# solenoid.net
KiCad netlist of a schematic drawn in Altium Designer
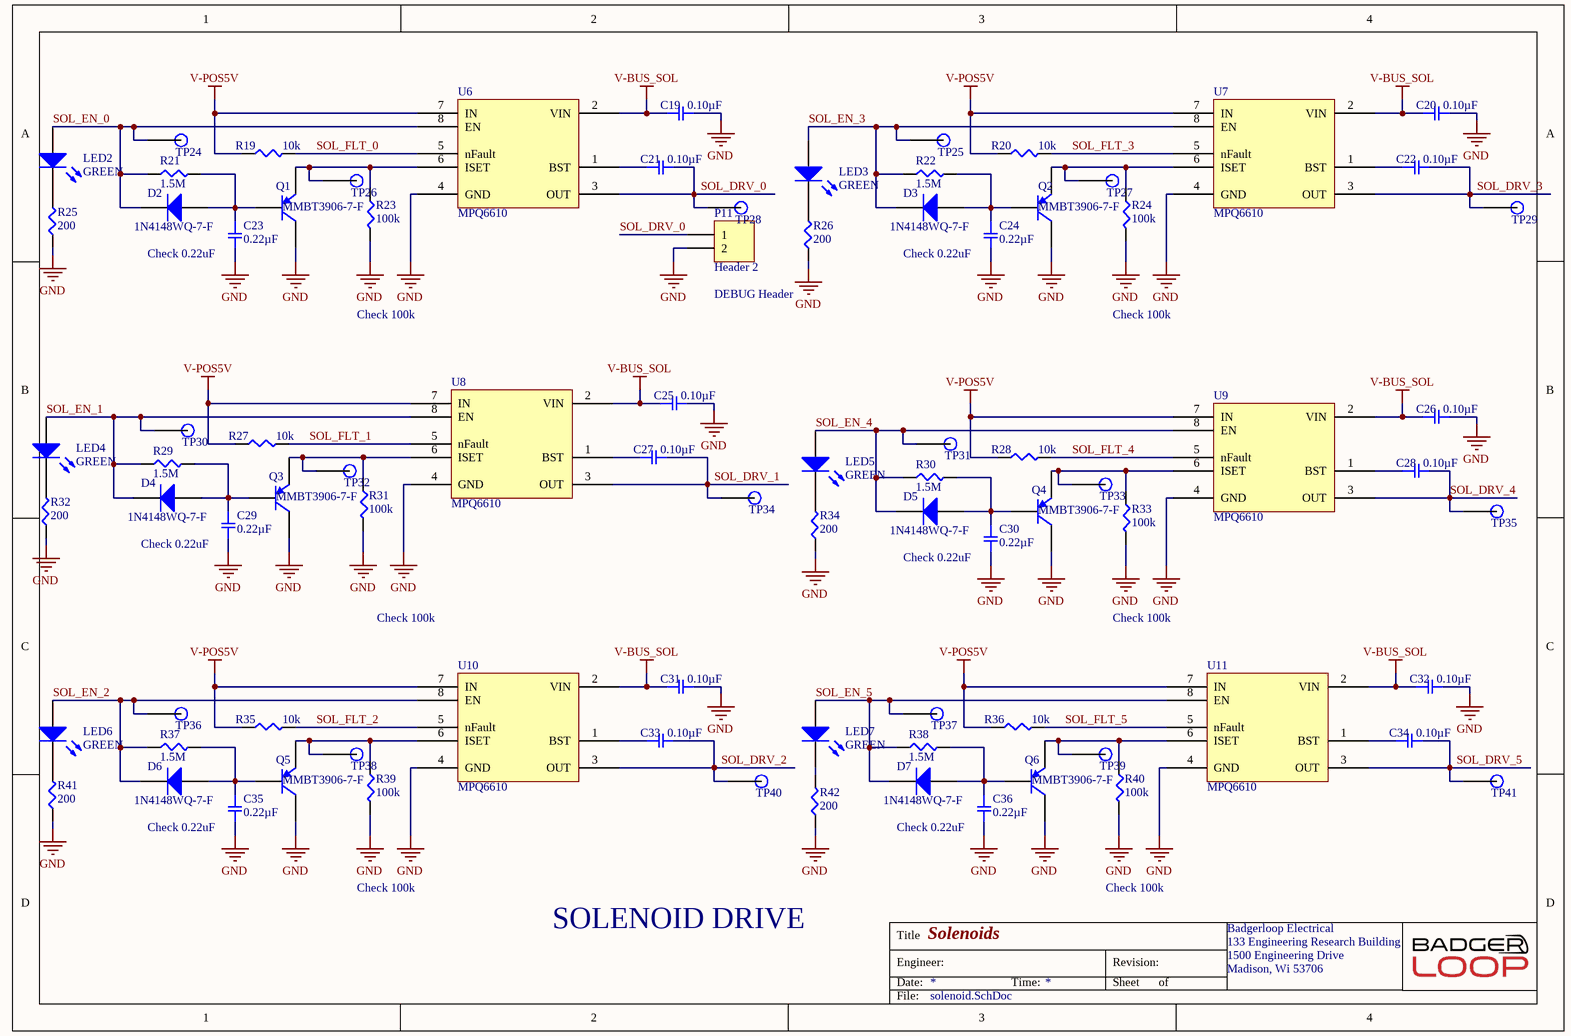
[diagram p0: solenoid.SchDoc]

(export (version "E")
  (design (tool "Eeschema 10.0.6"))
  (components
    (comp (ref "C19")
      (value "0.10µF")
      (footprint "SMD-0805C")
      (description "CAP CER 0.1UF 10V U2J 0805")
      (fields
        (field (name "DIGI-KEY PART NUMBER") "490-11592-1-ND")
        (field (name "PART NUMBER") "GRM21B7U1A104JA01L")
      )
      (libsource (lib "capacitors") (part "GRM21B7U1A104JA01L"))
    )
    (comp (ref "C20")
      (value "0.10µF")
      (footprint "SMD-0805C")
      (description "CAP CER 0.1UF 10V U2J 0805")
      (fields
        (field (name "DIGI-KEY PART NUMBER") "490-11592-1-ND")
        (field (name "PART NUMBER") "GRM21B7U1A104JA01L")
      )
      (libsource (lib "capacitors") (part "GRM21B7U1A104JA01L"))
    )
    (comp (ref "C21")
      (value "0.10µF")
      (footprint "SMD-0805C")
      (description "CAP CER 0.1UF 10V U2J 0805")
      (fields
        (field (name "DIGI-KEY PART NUMBER") "490-11592-1-ND")
        (field (name "PART NUMBER") "GRM21B7U1A104JA01L")
      )
      (libsource (lib "capacitors") (part "GRM21B7U1A104JA01L"))
    )
    (comp (ref "C22")
      (value "0.10µF")
      (footprint "SMD-0805C")
      (description "CAP CER 0.1UF 10V U2J 0805")
      (fields
        (field (name "DIGI-KEY PART NUMBER") "490-11592-1-ND")
        (field (name "PART NUMBER") "GRM21B7U1A104JA01L")
      )
      (libsource (lib "capacitors") (part "GRM21B7U1A104JA01L"))
    )
    (comp (ref "C23")
      (value "0.22µF")
      (footprint "SMD-0805C")
      (description "CAP CER 0.22UF 10V X7R 0805")
      (fields
        (field (name "DIGI-KEY PART NUMBER") "490-4432-1-ND")
        (field (name "PART NUMBER") "LLA215R71A224MA14L")
      )
      (libsource (lib "capacitors") (part "LLA215R71A224MA14L"))
    )
    (comp (ref "C24")
      (value "0.22µF")
      (footprint "SMD-0805C")
      (description "CAP CER 0.22UF 10V X7R 0805")
      (fields
        (field (name "DIGI-KEY PART NUMBER") "490-4432-1-ND")
        (field (name "PART NUMBER") "LLA215R71A224MA14L")
      )
      (libsource (lib "capacitors") (part "LLA215R71A224MA14L"))
    )
    (comp (ref "C25")
      (value "0.10µF")
      (footprint "SMD-0805C")
      (description "CAP CER 0.1UF 10V U2J 0805")
      (fields
        (field (name "DIGI-KEY PART NUMBER") "490-11592-1-ND")
        (field (name "PART NUMBER") "GRM21B7U1A104JA01L")
      )
      (libsource (lib "capacitors") (part "GRM21B7U1A104JA01L"))
    )
    (comp (ref "C26")
      (value "0.10µF")
      (footprint "SMD-0805C")
      (description "CAP CER 0.1UF 10V U2J 0805")
      (fields
        (field (name "DIGI-KEY PART NUMBER") "490-11592-1-ND")
        (field (name "PART NUMBER") "GRM21B7U1A104JA01L")
      )
      (libsource (lib "capacitors") (part "GRM21B7U1A104JA01L"))
    )
    (comp (ref "C27")
      (value "0.10µF")
      (footprint "SMD-0805C")
      (description "CAP CER 0.1UF 10V U2J 0805")
      (fields
        (field (name "DIGI-KEY PART NUMBER") "490-11592-1-ND")
        (field (name "PART NUMBER") "GRM21B7U1A104JA01L")
      )
      (libsource (lib "capacitors") (part "GRM21B7U1A104JA01L"))
    )
    (comp (ref "C28")
      (value "0.10µF")
      (footprint "SMD-0805C")
      (description "CAP CER 0.1UF 10V U2J 0805")
      (fields
        (field (name "DIGI-KEY PART NUMBER") "490-11592-1-ND")
        (field (name "PART NUMBER") "GRM21B7U1A104JA01L")
      )
      (libsource (lib "capacitors") (part "GRM21B7U1A104JA01L"))
    )
    (comp (ref "C29")
      (value "0.22µF")
      (footprint "SMD-0805C")
      (description "CAP CER 0.22UF 10V X7R 0805")
      (fields
        (field (name "DIGI-KEY PART NUMBER") "490-4432-1-ND")
        (field (name "PART NUMBER") "LLA215R71A224MA14L")
      )
      (libsource (lib "capacitors") (part "LLA215R71A224MA14L"))
    )
    (comp (ref "C30")
      (value "0.22µF")
      (footprint "SMD-0805C")
      (description "CAP CER 0.22UF 10V X7R 0805")
      (fields
        (field (name "DIGI-KEY PART NUMBER") "490-4432-1-ND")
        (field (name "PART NUMBER") "LLA215R71A224MA14L")
      )
      (libsource (lib "capacitors") (part "LLA215R71A224MA14L"))
    )
    (comp (ref "C31")
      (value "0.10µF")
      (footprint "SMD-0805C")
      (description "CAP CER 0.1UF 10V U2J 0805")
      (fields
        (field (name "DIGI-KEY PART NUMBER") "490-11592-1-ND")
        (field (name "PART NUMBER") "GRM21B7U1A104JA01L")
      )
      (libsource (lib "capacitors") (part "GRM21B7U1A104JA01L"))
    )
    (comp (ref "C32")
      (value "0.10µF")
      (footprint "SMD-0805C")
      (description "CAP CER 0.1UF 10V U2J 0805")
      (fields
        (field (name "DIGI-KEY PART NUMBER") "490-11592-1-ND")
        (field (name "PART NUMBER") "GRM21B7U1A104JA01L")
      )
      (libsource (lib "capacitors") (part "GRM21B7U1A104JA01L"))
    )
    (comp (ref "C33")
      (value "0.10µF")
      (footprint "SMD-0805C")
      (description "CAP CER 0.1UF 10V U2J 0805")
      (fields
        (field (name "DIGI-KEY PART NUMBER") "490-11592-1-ND")
        (field (name "PART NUMBER") "GRM21B7U1A104JA01L")
      )
      (libsource (lib "capacitors") (part "GRM21B7U1A104JA01L"))
    )
    (comp (ref "C34")
      (value "0.10µF")
      (footprint "SMD-0805C")
      (description "CAP CER 0.1UF 10V U2J 0805")
      (fields
        (field (name "DIGI-KEY PART NUMBER") "490-11592-1-ND")
        (field (name "PART NUMBER") "GRM21B7U1A104JA01L")
      )
      (libsource (lib "capacitors") (part "GRM21B7U1A104JA01L"))
    )
    (comp (ref "C35")
      (value "0.22µF")
      (footprint "SMD-0805C")
      (description "CAP CER 0.22UF 10V X7R 0805")
      (fields
        (field (name "DIGI-KEY PART NUMBER") "490-4432-1-ND")
        (field (name "PART NUMBER") "LLA215R71A224MA14L")
      )
      (libsource (lib "capacitors") (part "LLA215R71A224MA14L"))
    )
    (comp (ref "C36")
      (value "0.22µF")
      (footprint "SMD-0805C")
      (description "CAP CER 0.22UF 10V X7R 0805")
      (fields
        (field (name "DIGI-KEY PART NUMBER") "490-4432-1-ND")
        (field (name "PART NUMBER") "LLA215R71A224MA14L")
      )
      (libsource (lib "capacitors") (part "LLA215R71A224MA14L"))
    )
    (comp (ref "D2")
      (value "1N4148WQ-7-F")
      (footprint "SODFL350X80-2N")
      (description "Diodes - General Purpose, Power, Switching SMT Fast Switching Diode")
      (fields (field (name "MANUFACTURER") "Diodes Inc."))
      (libsource (lib "misc") (part "1N4148WQ-7-F"))
    )
    (comp (ref "D3")
      (value "1N4148WQ-7-F")
      (footprint "SODFL350X80-2N")
      (description "Diodes - General Purpose, Power, Switching SMT Fast Switching Diode")
      (fields (field (name "MANUFACTURER") "Diodes Inc."))
      (libsource (lib "misc") (part "1N4148WQ-7-F"))
    )
    (comp (ref "D4")
      (value "1N4148WQ-7-F")
      (footprint "SODFL350X80-2N")
      (description "Diodes - General Purpose, Power, Switching SMT Fast Switching Diode")
      (fields (field (name "MANUFACTURER") "Diodes Inc."))
      (libsource (lib "misc") (part "1N4148WQ-7-F"))
    )
    (comp (ref "D5")
      (value "1N4148WQ-7-F")
      (footprint "SODFL350X80-2N")
      (description "Diodes - General Purpose, Power, Switching SMT Fast Switching Diode")
      (fields (field (name "MANUFACTURER") "Diodes Inc."))
      (libsource (lib "misc") (part "1N4148WQ-7-F"))
    )
    (comp (ref "D6")
      (value "1N4148WQ-7-F")
      (footprint "SODFL350X80-2N")
      (description "Diodes - General Purpose, Power, Switching SMT Fast Switching Diode")
      (fields (field (name "MANUFACTURER") "Diodes Inc."))
      (libsource (lib "misc") (part "1N4148WQ-7-F"))
    )
    (comp (ref "D7")
      (value "1N4148WQ-7-F")
      (footprint "SODFL350X80-2N")
      (description "Diodes - General Purpose, Power, Switching SMT Fast Switching Diode")
      (fields (field (name "MANUFACTURER") "Diodes Inc."))
      (libsource (lib "misc") (part "1N4148WQ-7-F"))
    )
    (comp (ref "LED2")
      (value "GREEN")
      (footprint "LED 0603 GREEN")
      (fields (field (name "MANUFACTURER") "Lite-On Inc."))
      (libsource (lib "misc") (part "LED GREEN 0603"))
    )
    (comp (ref "LED3")
      (value "GREEN")
      (footprint "LED 0603 GREEN")
      (fields (field (name "MANUFACTURER") "Lite-On Inc."))
      (libsource (lib "misc") (part "LED GREEN 0603"))
    )
    (comp (ref "LED4")
      (value "GREEN")
      (footprint "LED 0603 GREEN")
      (fields (field (name "MANUFACTURER") "Lite-On Inc."))
      (libsource (lib "misc") (part "LED GREEN 0603"))
    )
    (comp (ref "LED5")
      (value "GREEN")
      (footprint "LED 0603 GREEN")
      (fields (field (name "MANUFACTURER") "Lite-On Inc."))
      (libsource (lib "misc") (part "LED GREEN 0603"))
    )
    (comp (ref "LED6")
      (value "GREEN")
      (footprint "LED 0603 GREEN")
      (fields (field (name "MANUFACTURER") "Lite-On Inc."))
      (libsource (lib "misc") (part "LED GREEN 0603"))
    )
    (comp (ref "LED7")
      (value "GREEN")
      (footprint "LED 0603 GREEN")
      (fields (field (name "MANUFACTURER") "Lite-On Inc."))
      (libsource (lib "misc") (part "LED GREEN 0603"))
    )
    (comp (ref "P11")
      (value "Header 2")
      (footprint "Pin Header 1x2 TH Pitch 2.54mm")
      (description "Header, 2-Pin")
      (fields (field (name "PUBLISHER") "Altium Limited"))
      (libsource (lib "connector") (part "Header 2"))
    )
    (comp (ref "Q1")
      (value "MMBT3906-7-F")
      (footprint "SOTFL103P240X110-3N")
      (fields (field (name "MANUFACTURER") "Diodes Zetex"))
      (libsource (lib "misc") (part "MMBT3906-7-F"))
    )
    (comp (ref "Q2")
      (value "MMBT3906-7-F")
      (footprint "SOTFL103P240X110-3N")
      (fields (field (name "MANUFACTURER") "Diodes Zetex"))
      (libsource (lib "misc") (part "MMBT3906-7-F"))
    )
    (comp (ref "Q3")
      (value "MMBT3906-7-F")
      (footprint "SOTFL103P240X110-3N")
      (fields (field (name "MANUFACTURER") "Diodes Zetex"))
      (libsource (lib "misc") (part "MMBT3906-7-F"))
    )
    (comp (ref "Q4")
      (value "MMBT3906-7-F")
      (footprint "SOTFL103P240X110-3N")
      (fields (field (name "MANUFACTURER") "Diodes Zetex"))
      (libsource (lib "misc") (part "MMBT3906-7-F"))
    )
    (comp (ref "Q5")
      (value "MMBT3906-7-F")
      (footprint "SOTFL103P240X110-3N")
      (fields (field (name "MANUFACTURER") "Diodes Zetex"))
      (libsource (lib "misc") (part "MMBT3906-7-F"))
    )
    (comp (ref "Q6")
      (value "MMBT3906-7-F")
      (footprint "SOTFL103P240X110-3N")
      (fields (field (name "MANUFACTURER") "Diodes Zetex"))
      (libsource (lib "misc") (part "MMBT3906-7-F"))
    )
    (comp (ref "R19")
      (value "10k")
      (footprint "SMD-0805-RES")
      (description "RES SMD 10K OHM 5% 1/2W 0805")
      (fields (field (name "PART NUMBER") "ERJ-P06J103V") (field (name "DIGI-KEY PART NUMBER") "P10KADCT-ND"))
      (libsource (lib "resistors") (part "ERJ-P06J103V"))
    )
    (comp (ref "R20")
      (value "10k")
      (footprint "SMD-0805-RES")
      (description "RES SMD 10K OHM 5% 1/2W 0805")
      (fields (field (name "PART NUMBER") "ERJ-P06J103V") (field (name "DIGI-KEY PART NUMBER") "P10KADCT-ND"))
      (libsource (lib "resistors") (part "ERJ-P06J103V"))
    )
    (comp (ref "R21")
      (value "1.5M")
      (footprint "SMD-0805-RES")
      (description "RES SMD 1.5M OHM 5% 1/8W 0805")
      (fields
        (field (name "PART NUMBER") "ERJ-6GEYJ155V")
        (field (name "DIGI-KEY PART NUMBER") "P1.5MACT-ND")
      )
      (libsource (lib "resistors") (part "ERJ-6GEYJ155V"))
    )
    (comp (ref "R22")
      (value "1.5M")
      (footprint "SMD-0805-RES")
      (description "RES SMD 1.5M OHM 5% 1/8W 0805")
      (fields
        (field (name "PART NUMBER") "ERJ-6GEYJ155V")
        (field (name "DIGI-KEY PART NUMBER") "P1.5MACT-ND")
      )
      (libsource (lib "resistors") (part "ERJ-6GEYJ155V"))
    )
    (comp (ref "R23")
      (value "100k")
      (footprint "SMD-0805-RES")
      (description "RES SMD 100K OHM 5% 1/2W 0805")
      (fields
        (field (name "PART NUMBER") "ERJ-P06J104V")
        (field (name "DIGI-KEY PART NUMBER") "P100KADCT-ND")
      )
      (libsource (lib "resistors") (part "ERJ-P06J104V"))
    )
    (comp (ref "R24")
      (value "100k")
      (footprint "SMD-0805-RES")
      (description "RES SMD 100K OHM 5% 1/2W 0805")
      (fields
        (field (name "PART NUMBER") "ERJ-P06J104V")
        (field (name "DIGI-KEY PART NUMBER") "P100KADCT-ND")
      )
      (libsource (lib "resistors") (part "ERJ-P06J104V"))
    )
    (comp (ref "R25")
      (value "200")
      (footprint "SMD-0805-RES")
      (description "RES SMD 200 OHM 1% 1/2W 0805")
      (fields
        (field (name "PART NUMBER") "ERJ-P06F2000V")
        (field (name "DIGI-KEY PART NUMBER") "P16064CT-ND")
      )
      (libsource (lib "resistors") (part "ERJ-P06F2000V"))
    )
    (comp (ref "R26")
      (value "200")
      (footprint "SMD-0805-RES")
      (description "RES SMD 200 OHM 1% 1/2W 0805")
      (fields
        (field (name "PART NUMBER") "ERJ-P06F2000V")
        (field (name "DIGI-KEY PART NUMBER") "P16064CT-ND")
      )
      (libsource (lib "resistors") (part "ERJ-P06F2000V"))
    )
    (comp (ref "R27")
      (value "10k")
      (footprint "SMD-0805-RES")
      (description "RES SMD 10K OHM 5% 1/2W 0805")
      (fields (field (name "PART NUMBER") "ERJ-P06J103V") (field (name "DIGI-KEY PART NUMBER") "P10KADCT-ND"))
      (libsource (lib "resistors") (part "ERJ-P06J103V"))
    )
    (comp (ref "R28")
      (value "10k")
      (footprint "SMD-0805-RES")
      (description "RES SMD 10K OHM 5% 1/2W 0805")
      (fields (field (name "PART NUMBER") "ERJ-P06J103V") (field (name "DIGI-KEY PART NUMBER") "P10KADCT-ND"))
      (libsource (lib "resistors") (part "ERJ-P06J103V"))
    )
    (comp (ref "R29")
      (value "1.5M")
      (footprint "SMD-0805-RES")
      (description "RES SMD 1.5M OHM 5% 1/8W 0805")
      (fields
        (field (name "PART NUMBER") "ERJ-6GEYJ155V")
        (field (name "DIGI-KEY PART NUMBER") "P1.5MACT-ND")
      )
      (libsource (lib "resistors") (part "ERJ-6GEYJ155V"))
    )
    (comp (ref "R30")
      (value "1.5M")
      (footprint "SMD-0805-RES")
      (description "RES SMD 1.5M OHM 5% 1/8W 0805")
      (fields
        (field (name "PART NUMBER") "ERJ-6GEYJ155V")
        (field (name "DIGI-KEY PART NUMBER") "P1.5MACT-ND")
      )
      (libsource (lib "resistors") (part "ERJ-6GEYJ155V"))
    )
    (comp (ref "R31")
      (value "100k")
      (footprint "SMD-0805-RES")
      (description "RES SMD 100K OHM 5% 1/2W 0805")
      (fields
        (field (name "PART NUMBER") "ERJ-P06J104V")
        (field (name "DIGI-KEY PART NUMBER") "P100KADCT-ND")
      )
      (libsource (lib "resistors") (part "ERJ-P06J104V"))
    )
    (comp (ref "R32")
      (value "200")
      (footprint "SMD-0805-RES")
      (description "RES SMD 200 OHM 1% 1/2W 0805")
      (fields
        (field (name "PART NUMBER") "ERJ-P06F2000V")
        (field (name "DIGI-KEY PART NUMBER") "P16064CT-ND")
      )
      (libsource (lib "resistors") (part "ERJ-P06F2000V"))
    )
    (comp (ref "R33")
      (value "100k")
      (footprint "SMD-0805-RES")
      (description "RES SMD 100K OHM 5% 1/2W 0805")
      (fields
        (field (name "PART NUMBER") "ERJ-P06J104V")
        (field (name "DIGI-KEY PART NUMBER") "P100KADCT-ND")
      )
      (libsource (lib "resistors") (part "ERJ-P06J104V"))
    )
    (comp (ref "R34")
      (value "200")
      (footprint "SMD-0805-RES")
      (description "RES SMD 200 OHM 1% 1/2W 0805")
      (fields
        (field (name "PART NUMBER") "ERJ-P06F2000V")
        (field (name "DIGI-KEY PART NUMBER") "P16064CT-ND")
      )
      (libsource (lib "resistors") (part "ERJ-P06F2000V"))
    )
    (comp (ref "R35")
      (value "10k")
      (footprint "SMD-0805-RES")
      (description "RES SMD 10K OHM 5% 1/2W 0805")
      (fields (field (name "PART NUMBER") "ERJ-P06J103V") (field (name "DIGI-KEY PART NUMBER") "P10KADCT-ND"))
      (libsource (lib "resistors") (part "ERJ-P06J103V"))
    )
    (comp (ref "R36")
      (value "10k")
      (footprint "SMD-0805-RES")
      (description "RES SMD 10K OHM 5% 1/2W 0805")
      (fields (field (name "PART NUMBER") "ERJ-P06J103V") (field (name "DIGI-KEY PART NUMBER") "P10KADCT-ND"))
      (libsource (lib "resistors") (part "ERJ-P06J103V"))
    )
    (comp (ref "R37")
      (value "1.5M")
      (footprint "SMD-0805-RES")
      (description "RES SMD 1.5M OHM 5% 1/8W 0805")
      (fields
        (field (name "PART NUMBER") "ERJ-6GEYJ155V")
        (field (name "DIGI-KEY PART NUMBER") "P1.5MACT-ND")
      )
      (libsource (lib "resistors") (part "ERJ-6GEYJ155V"))
    )
    (comp (ref "R38")
      (value "1.5M")
      (footprint "SMD-0805-RES")
      (description "RES SMD 1.5M OHM 5% 1/8W 0805")
      (fields
        (field (name "PART NUMBER") "ERJ-6GEYJ155V")
        (field (name "DIGI-KEY PART NUMBER") "P1.5MACT-ND")
      )
      (libsource (lib "resistors") (part "ERJ-6GEYJ155V"))
    )
    (comp (ref "R39")
      (value "100k")
      (footprint "SMD-0805-RES")
      (description "RES SMD 100K OHM 5% 1/2W 0805")
      (fields
        (field (name "PART NUMBER") "ERJ-P06J104V")
        (field (name "DIGI-KEY PART NUMBER") "P100KADCT-ND")
      )
      (libsource (lib "resistors") (part "ERJ-P06J104V"))
    )
    (comp (ref "R40")
      (value "100k")
      (footprint "SMD-0805-RES")
      (description "RES SMD 100K OHM 5% 1/2W 0805")
      (fields
        (field (name "PART NUMBER") "ERJ-P06J104V")
        (field (name "DIGI-KEY PART NUMBER") "P100KADCT-ND")
      )
      (libsource (lib "resistors") (part "ERJ-P06J104V"))
    )
    (comp (ref "R41")
      (value "200")
      (footprint "SMD-0805-RES")
      (description "RES SMD 200 OHM 1% 1/2W 0805")
      (fields
        (field (name "PART NUMBER") "ERJ-P06F2000V")
        (field (name "DIGI-KEY PART NUMBER") "P16064CT-ND")
      )
      (libsource (lib "resistors") (part "ERJ-P06F2000V"))
    )
    (comp (ref "R42")
      (value "200")
      (footprint "SMD-0805-RES")
      (description "RES SMD 200 OHM 1% 1/2W 0805")
      (fields
        (field (name "PART NUMBER") "ERJ-P06F2000V")
        (field (name "DIGI-KEY PART NUMBER") "P16064CT-ND")
      )
      (libsource (lib "resistors") (part "ERJ-P06F2000V"))
    )
    (comp (ref "TP24")
      (value "TP")
      (footprint "Test Point")
      (description "SMD TEST POINT")
      (libsource (lib "misc") (part "TP"))
    )
    (comp (ref "TP25")
      (value "TP")
      (footprint "Test Point")
      (description "SMD TEST POINT")
      (libsource (lib "misc") (part "TP"))
    )
    (comp (ref "TP26")
      (value "TP")
      (footprint "Test Point")
      (description "SMD TEST POINT")
      (libsource (lib "misc") (part "TP"))
    )
    (comp (ref "TP27")
      (value "TP")
      (footprint "Test Point")
      (description "SMD TEST POINT")
      (libsource (lib "misc") (part "TP"))
    )
    (comp (ref "TP28")
      (value "TP")
      (footprint "Test Point")
      (description "SMD TEST POINT")
      (libsource (lib "misc") (part "TP"))
    )
    (comp (ref "TP29")
      (value "TP")
      (footprint "Test Point")
      (description "SMD TEST POINT")
      (libsource (lib "misc") (part "TP"))
    )
    (comp (ref "TP30")
      (value "TP")
      (footprint "Test Point")
      (description "SMD TEST POINT")
      (libsource (lib "misc") (part "TP"))
    )
    (comp (ref "TP31")
      (value "TP")
      (footprint "Test Point")
      (description "SMD TEST POINT")
      (libsource (lib "misc") (part "TP"))
    )
    (comp (ref "TP32")
      (value "TP")
      (footprint "Test Point")
      (description "SMD TEST POINT")
      (libsource (lib "misc") (part "TP"))
    )
    (comp (ref "TP33")
      (value "TP")
      (footprint "Test Point")
      (description "SMD TEST POINT")
      (libsource (lib "misc") (part "TP"))
    )
    (comp (ref "TP34")
      (value "TP")
      (footprint "Test Point")
      (description "SMD TEST POINT")
      (libsource (lib "misc") (part "TP"))
    )
    (comp (ref "TP35")
      (value "TP")
      (footprint "Test Point")
      (description "SMD TEST POINT")
      (libsource (lib "misc") (part "TP"))
    )
    (comp (ref "TP36")
      (value "TP")
      (footprint "Test Point")
      (description "SMD TEST POINT")
      (libsource (lib "misc") (part "TP"))
    )
    (comp (ref "TP37")
      (value "TP")
      (footprint "Test Point")
      (description "SMD TEST POINT")
      (libsource (lib "misc") (part "TP"))
    )
    (comp (ref "TP38")
      (value "TP")
      (footprint "Test Point")
      (description "SMD TEST POINT")
      (libsource (lib "misc") (part "TP"))
    )
    (comp (ref "TP39")
      (value "TP")
      (footprint "Test Point")
      (description "SMD TEST POINT")
      (libsource (lib "misc") (part "TP"))
    )
    (comp (ref "TP40")
      (value "TP")
      (footprint "Test Point")
      (description "SMD TEST POINT")
      (libsource (lib "misc") (part "TP"))
    )
    (comp (ref "TP41")
      (value "TP")
      (footprint "Test Point")
      (description "SMD TEST POINT")
      (libsource (lib "misc") (part "TP"))
    )
    (comp (ref "U6")
      (value "MPQ6610")
      (footprint "SOP127P600X175-8N")
      (libsource (lib "ic") (part "MPQ6610"))
    )
    (comp (ref "U7")
      (value "MPQ6610")
      (footprint "SOP127P600X175-8N")
      (libsource (lib "ic") (part "MPQ6610"))
    )
    (comp (ref "U8")
      (value "MPQ6610")
      (footprint "SOP127P600X175-8N")
      (libsource (lib "ic") (part "MPQ6610"))
    )
    (comp (ref "U9")
      (value "MPQ6610")
      (footprint "SOP127P600X175-8N")
      (libsource (lib "ic") (part "MPQ6610"))
    )
    (comp (ref "U10")
      (value "MPQ6610")
      (footprint "SOP127P600X175-8N")
      (libsource (lib "ic") (part "MPQ6610"))
    )
    (comp (ref "U11")
      (value "MPQ6610")
      (footprint "SOP127P600X175-8N")
      (libsource (lib "ic") (part "MPQ6610"))
    )
  )
  (nets
    (net (code "1") (name "/SOL_DRV_0") (class "Default")
      (node (ref "C21") (pin "2") (pinfunction "2_2") (pintype "passive"))
      (node (ref "P11") (pin "1") (pinfunction "1_1") (pintype "passive"))
      (node (ref "TP28") (pin "1") (pinfunction "1_1") (pintype "passive"))
      (node (ref "U6") (pin "3") (pinfunction "OUT_3") (pintype "passive"))
    )
    (net (code "2") (name "/SOL_DRV_1") (class "Default")
      (node (ref "C27") (pin "2") (pinfunction "2_2") (pintype "passive"))
      (node (ref "TP34") (pin "1") (pinfunction "1_1") (pintype "passive"))
      (node (ref "U8") (pin "3") (pinfunction "OUT_3") (pintype "passive"))
    )
    (net (code "3") (name "/SOL_DRV_2") (class "Default")
      (node (ref "C33") (pin "2") (pinfunction "2_2") (pintype "passive"))
      (node (ref "TP40") (pin "1") (pinfunction "1_1") (pintype "passive"))
      (node (ref "U10") (pin "3") (pinfunction "OUT_3") (pintype "passive"))
    )
    (net (code "4") (name "/SOL_DRV_3") (class "Default")
      (node (ref "C22") (pin "2") (pinfunction "2_2") (pintype "passive"))
      (node (ref "TP29") (pin "1") (pinfunction "1_1") (pintype "passive"))
      (node (ref "U7") (pin "3") (pinfunction "OUT_3") (pintype "passive"))
    )
    (net (code "5") (name "/SOL_DRV_4") (class "Default")
      (node (ref "C28") (pin "2") (pinfunction "2_2") (pintype "passive"))
      (node (ref "TP35") (pin "1") (pinfunction "1_1") (pintype "passive"))
      (node (ref "U9") (pin "3") (pinfunction "OUT_3") (pintype "passive"))
    )
    (net (code "6") (name "/SOL_DRV_5") (class "Default")
      (node (ref "C34") (pin "2") (pinfunction "2_2") (pintype "passive"))
      (node (ref "TP41") (pin "1") (pinfunction "1_1") (pintype "passive"))
      (node (ref "U11") (pin "3") (pinfunction "OUT_3") (pintype "passive"))
    )
    (net (code "7") (name "/SOL_EN_0") (class "Default")
      (node (ref "D2") (pin "2") (pinfunction "K_2") (pintype "passive"))
      (node (ref "LED2") (pin "1") (pinfunction "A_1") (pintype "passive"))
      (node (ref "R21") (pin "1") (pinfunction "1_1") (pintype "passive"))
      (node (ref "TP24") (pin "1") (pinfunction "1_1") (pintype "passive"))
      (node (ref "U6") (pin "8") (pinfunction "EN_8") (pintype "power_in"))
    )
    (net (code "8") (name "/SOL_EN_1") (class "Default")
      (node (ref "D4") (pin "2") (pinfunction "K_2") (pintype "passive"))
      (node (ref "LED4") (pin "1") (pinfunction "A_1") (pintype "passive"))
      (node (ref "R29") (pin "1") (pinfunction "1_1") (pintype "passive"))
      (node (ref "TP30") (pin "1") (pinfunction "1_1") (pintype "passive"))
      (node (ref "U8") (pin "8") (pinfunction "EN_8") (pintype "power_in"))
    )
    (net (code "9") (name "/SOL_EN_2") (class "Default")
      (node (ref "D6") (pin "2") (pinfunction "K_2") (pintype "passive"))
      (node (ref "LED6") (pin "1") (pinfunction "A_1") (pintype "passive"))
      (node (ref "R37") (pin "1") (pinfunction "1_1") (pintype "passive"))
      (node (ref "TP36") (pin "1") (pinfunction "1_1") (pintype "passive"))
      (node (ref "U10") (pin "8") (pinfunction "EN_8") (pintype "power_in"))
    )
    (net (code "10") (name "/SOL_EN_3") (class "Default")
      (node (ref "D3") (pin "2") (pinfunction "K_2") (pintype "passive"))
      (node (ref "LED3") (pin "1") (pinfunction "A_1") (pintype "passive"))
      (node (ref "R22") (pin "1") (pinfunction "1_1") (pintype "passive"))
      (node (ref "TP25") (pin "1") (pinfunction "1_1") (pintype "passive"))
      (node (ref "U7") (pin "8") (pinfunction "EN_8") (pintype "power_in"))
    )
    (net (code "11") (name "/SOL_EN_4") (class "Default")
      (node (ref "D5") (pin "2") (pinfunction "K_2") (pintype "passive"))
      (node (ref "LED5") (pin "1") (pinfunction "A_1") (pintype "passive"))
      (node (ref "R30") (pin "1") (pinfunction "1_1") (pintype "passive"))
      (node (ref "TP31") (pin "1") (pinfunction "1_1") (pintype "passive"))
      (node (ref "U9") (pin "8") (pinfunction "EN_8") (pintype "power_in"))
    )
    (net (code "12") (name "/SOL_EN_5") (class "Default")
      (node (ref "D7") (pin "2") (pinfunction "K_2") (pintype "passive"))
      (node (ref "LED7") (pin "1") (pinfunction "A_1") (pintype "passive"))
      (node (ref "R38") (pin "1") (pinfunction "1_1") (pintype "passive"))
      (node (ref "TP37") (pin "1") (pinfunction "1_1") (pintype "passive"))
      (node (ref "U11") (pin "8") (pinfunction "EN_8") (pintype "power_in"))
    )
    (net (code "13") (name "/SOL_FLT_0") (class "Default")
      (node (ref "R19") (pin "2") (pinfunction "2_2") (pintype "passive"))
      (node (ref "U6") (pin "5") (pinfunction "nFault_5") (pintype "passive"))
    )
    (net (code "14") (name "/SOL_FLT_1") (class "Default")
      (node (ref "R27") (pin "2") (pinfunction "2_2") (pintype "passive"))
      (node (ref "U8") (pin "5") (pinfunction "nFault_5") (pintype "passive"))
    )
    (net (code "15") (name "/SOL_FLT_2") (class "Default")
      (node (ref "R35") (pin "2") (pinfunction "2_2") (pintype "passive"))
      (node (ref "U10") (pin "5") (pinfunction "nFault_5") (pintype "passive"))
    )
    (net (code "16") (name "/SOL_FLT_3") (class "Default")
      (node (ref "R20") (pin "2") (pinfunction "2_2") (pintype "passive"))
      (node (ref "U7") (pin "5") (pinfunction "nFault_5") (pintype "passive"))
    )
    (net (code "17") (name "/SOL_FLT_4") (class "Default")
      (node (ref "R28") (pin "2") (pinfunction "2_2") (pintype "passive"))
      (node (ref "U9") (pin "5") (pinfunction "nFault_5") (pintype "passive"))
    )
    (net (code "18") (name "/SOL_FLT_5") (class "Default")
      (node (ref "R36") (pin "2") (pinfunction "2_2") (pintype "passive"))
      (node (ref "U11") (pin "5") (pinfunction "nFault_5") (pintype "passive"))
    )
    (net (code "19") (name "GND") (class "Default")
      (node (ref "C19") (pin "2") (pinfunction "2_2") (pintype "passive"))
      (node (ref "C20") (pin "2") (pinfunction "2_2") (pintype "passive"))
      (node (ref "C23") (pin "2") (pinfunction "2_2") (pintype "passive"))
      (node (ref "C24") (pin "2") (pinfunction "2_2") (pintype "passive"))
      (node (ref "C25") (pin "2") (pinfunction "2_2") (pintype "passive"))
      (node (ref "C26") (pin "2") (pinfunction "2_2") (pintype "passive"))
      (node (ref "C29") (pin "2") (pinfunction "2_2") (pintype "passive"))
      (node (ref "C30") (pin "2") (pinfunction "2_2") (pintype "passive"))
      (node (ref "C31") (pin "2") (pinfunction "2_2") (pintype "passive"))
      (node (ref "C32") (pin "2") (pinfunction "2_2") (pintype "passive"))
      (node (ref "C35") (pin "2") (pinfunction "2_2") (pintype "passive"))
      (node (ref "C36") (pin "2") (pinfunction "2_2") (pintype "passive"))
      (node (ref "P11") (pin "2") (pinfunction "2_2") (pintype "passive"))
      (node (ref "Q1") (pin "3") (pinfunction "C_3") (pintype "passive"))
      (node (ref "Q2") (pin "3") (pinfunction "C_3") (pintype "passive"))
      (node (ref "Q3") (pin "3") (pinfunction "C_3") (pintype "passive"))
      (node (ref "Q4") (pin "3") (pinfunction "C_3") (pintype "passive"))
      (node (ref "Q5") (pin "3") (pinfunction "C_3") (pintype "passive"))
      (node (ref "Q6") (pin "3") (pinfunction "C_3") (pintype "passive"))
      (node (ref "R23") (pin "2") (pinfunction "2_2") (pintype "passive"))
      (node (ref "R24") (pin "2") (pinfunction "2_2") (pintype "passive"))
      (node (ref "R25") (pin "1") (pinfunction "1_1") (pintype "passive"))
      (node (ref "R26") (pin "1") (pinfunction "1_1") (pintype "passive"))
      (node (ref "R31") (pin "2") (pinfunction "2_2") (pintype "passive"))
      (node (ref "R32") (pin "1") (pinfunction "1_1") (pintype "passive"))
      (node (ref "R33") (pin "2") (pinfunction "2_2") (pintype "passive"))
      (node (ref "R34") (pin "1") (pinfunction "1_1") (pintype "passive"))
      (node (ref "R39") (pin "2") (pinfunction "2_2") (pintype "passive"))
      (node (ref "R40") (pin "2") (pinfunction "2_2") (pintype "passive"))
      (node (ref "R41") (pin "1") (pinfunction "1_1") (pintype "passive"))
      (node (ref "R42") (pin "1") (pinfunction "1_1") (pintype "passive"))
      (node (ref "U10") (pin "4") (pinfunction "GND_4") (pintype "passive"))
      (node (ref "U11") (pin "4") (pinfunction "GND_4") (pintype "passive"))
      (node (ref "U6") (pin "4") (pinfunction "GND_4") (pintype "passive"))
      (node (ref "U7") (pin "4") (pinfunction "GND_4") (pintype "passive"))
      (node (ref "U8") (pin "4") (pinfunction "GND_4") (pintype "passive"))
      (node (ref "U9") (pin "4") (pinfunction "GND_4") (pintype "passive"))
    )
    (net (code "20") (name "Net-(D2-A)") (class "Default")
      (node (ref "C23") (pin "1") (pinfunction "1_1") (pintype "passive"))
      (node (ref "D2") (pin "1") (pinfunction "A_1") (pintype "passive"))
      (node (ref "Q1") (pin "1") (pinfunction "B_1") (pintype "passive"))
      (node (ref "R21") (pin "2") (pinfunction "2_2") (pintype "passive"))
    )
    (net (code "21") (name "Net-(D3-A)") (class "Default")
      (node (ref "C24") (pin "1") (pinfunction "1_1") (pintype "passive"))
      (node (ref "D3") (pin "1") (pinfunction "A_1") (pintype "passive"))
      (node (ref "Q2") (pin "1") (pinfunction "B_1") (pintype "passive"))
      (node (ref "R22") (pin "2") (pinfunction "2_2") (pintype "passive"))
    )
    (net (code "22") (name "Net-(D4-A)") (class "Default")
      (node (ref "C29") (pin "1") (pinfunction "1_1") (pintype "passive"))
      (node (ref "D4") (pin "1") (pinfunction "A_1") (pintype "passive"))
      (node (ref "Q3") (pin "1") (pinfunction "B_1") (pintype "passive"))
      (node (ref "R29") (pin "2") (pinfunction "2_2") (pintype "passive"))
    )
    (net (code "23") (name "Net-(D5-A)") (class "Default")
      (node (ref "C30") (pin "1") (pinfunction "1_1") (pintype "passive"))
      (node (ref "D5") (pin "1") (pinfunction "A_1") (pintype "passive"))
      (node (ref "Q4") (pin "1") (pinfunction "B_1") (pintype "passive"))
      (node (ref "R30") (pin "2") (pinfunction "2_2") (pintype "passive"))
    )
    (net (code "24") (name "Net-(D6-A)") (class "Default")
      (node (ref "C35") (pin "1") (pinfunction "1_1") (pintype "passive"))
      (node (ref "D6") (pin "1") (pinfunction "A_1") (pintype "passive"))
      (node (ref "Q5") (pin "1") (pinfunction "B_1") (pintype "passive"))
      (node (ref "R37") (pin "2") (pinfunction "2_2") (pintype "passive"))
    )
    (net (code "25") (name "Net-(D7-A)") (class "Default")
      (node (ref "C36") (pin "1") (pinfunction "1_1") (pintype "passive"))
      (node (ref "D7") (pin "1") (pinfunction "A_1") (pintype "passive"))
      (node (ref "Q6") (pin "1") (pinfunction "B_1") (pintype "passive"))
      (node (ref "R38") (pin "2") (pinfunction "2_2") (pintype "passive"))
    )
    (net (code "26") (name "Net-(LED2-K)") (class "Default")
      (node (ref "LED2") (pin "2") (pinfunction "K_2") (pintype "passive"))
      (node (ref "R25") (pin "2") (pinfunction "2_2") (pintype "passive"))
    )
    (net (code "27") (name "Net-(LED3-K)") (class "Default")
      (node (ref "LED3") (pin "2") (pinfunction "K_2") (pintype "passive"))
      (node (ref "R26") (pin "2") (pinfunction "2_2") (pintype "passive"))
    )
    (net (code "28") (name "Net-(LED4-K)") (class "Default")
      (node (ref "LED4") (pin "2") (pinfunction "K_2") (pintype "passive"))
      (node (ref "R32") (pin "2") (pinfunction "2_2") (pintype "passive"))
    )
    (net (code "29") (name "Net-(LED5-K)") (class "Default")
      (node (ref "LED5") (pin "2") (pinfunction "K_2") (pintype "passive"))
      (node (ref "R34") (pin "2") (pinfunction "2_2") (pintype "passive"))
    )
    (net (code "30") (name "Net-(LED6-K)") (class "Default")
      (node (ref "LED6") (pin "2") (pinfunction "K_2") (pintype "passive"))
      (node (ref "R41") (pin "2") (pinfunction "2_2") (pintype "passive"))
    )
    (net (code "31") (name "Net-(LED7-K)") (class "Default")
      (node (ref "LED7") (pin "2") (pinfunction "K_2") (pintype "passive"))
      (node (ref "R42") (pin "2") (pinfunction "2_2") (pintype "passive"))
    )
    (net (code "32") (name "Net-(Q1-E)") (class "Default")
      (node (ref "Q1") (pin "2") (pinfunction "E_2") (pintype "passive"))
      (node (ref "R23") (pin "1") (pinfunction "1_1") (pintype "passive"))
      (node (ref "TP26") (pin "1") (pinfunction "1_1") (pintype "passive"))
      (node (ref "U6") (pin "6") (pinfunction "ISET_6") (pintype "power_in"))
    )
    (net (code "33") (name "Net-(Q2-E)") (class "Default")
      (node (ref "Q2") (pin "2") (pinfunction "E_2") (pintype "passive"))
      (node (ref "R24") (pin "1") (pinfunction "1_1") (pintype "passive"))
      (node (ref "TP27") (pin "1") (pinfunction "1_1") (pintype "passive"))
      (node (ref "U7") (pin "6") (pinfunction "ISET_6") (pintype "power_in"))
    )
    (net (code "34") (name "Net-(Q3-E)") (class "Default")
      (node (ref "Q3") (pin "2") (pinfunction "E_2") (pintype "passive"))
      (node (ref "R31") (pin "1") (pinfunction "1_1") (pintype "passive"))
      (node (ref "TP32") (pin "1") (pinfunction "1_1") (pintype "passive"))
      (node (ref "U8") (pin "6") (pinfunction "ISET_6") (pintype "power_in"))
    )
    (net (code "35") (name "Net-(Q4-E)") (class "Default")
      (node (ref "Q4") (pin "2") (pinfunction "E_2") (pintype "passive"))
      (node (ref "R33") (pin "1") (pinfunction "1_1") (pintype "passive"))
      (node (ref "TP33") (pin "1") (pinfunction "1_1") (pintype "passive"))
      (node (ref "U9") (pin "6") (pinfunction "ISET_6") (pintype "power_in"))
    )
    (net (code "36") (name "Net-(Q5-E)") (class "Default")
      (node (ref "Q5") (pin "2") (pinfunction "E_2") (pintype "passive"))
      (node (ref "R39") (pin "1") (pinfunction "1_1") (pintype "passive"))
      (node (ref "TP38") (pin "1") (pinfunction "1_1") (pintype "passive"))
      (node (ref "U10") (pin "6") (pinfunction "ISET_6") (pintype "power_in"))
    )
    (net (code "37") (name "Net-(Q6-E)") (class "Default")
      (node (ref "Q6") (pin "2") (pinfunction "E_2") (pintype "passive"))
      (node (ref "R40") (pin "1") (pinfunction "1_1") (pintype "passive"))
      (node (ref "TP39") (pin "1") (pinfunction "1_1") (pintype "passive"))
      (node (ref "U11") (pin "6") (pinfunction "ISET_6") (pintype "power_in"))
    )
    (net (code "38") (name "Net-(U6-BST)") (class "Default")
      (node (ref "C21") (pin "1") (pinfunction "1_1") (pintype "passive"))
      (node (ref "U6") (pin "1") (pinfunction "BST_1") (pintype "passive"))
    )
    (net (code "39") (name "Net-(U7-BST)") (class "Default")
      (node (ref "C22") (pin "1") (pinfunction "1_1") (pintype "passive"))
      (node (ref "U7") (pin "1") (pinfunction "BST_1") (pintype "passive"))
    )
    (net (code "40") (name "Net-(U8-BST)") (class "Default")
      (node (ref "C27") (pin "1") (pinfunction "1_1") (pintype "passive"))
      (node (ref "U8") (pin "1") (pinfunction "BST_1") (pintype "passive"))
    )
    (net (code "41") (name "Net-(U9-BST)") (class "Default")
      (node (ref "C28") (pin "1") (pinfunction "1_1") (pintype "passive"))
      (node (ref "U9") (pin "1") (pinfunction "BST_1") (pintype "passive"))
    )
    (net (code "42") (name "Net-(U10-BST)") (class "Default")
      (node (ref "C33") (pin "1") (pinfunction "1_1") (pintype "passive"))
      (node (ref "U10") (pin "1") (pinfunction "BST_1") (pintype "passive"))
    )
    (net (code "43") (name "Net-(U11-BST)") (class "Default")
      (node (ref "C34") (pin "1") (pinfunction "1_1") (pintype "passive"))
      (node (ref "U11") (pin "1") (pinfunction "BST_1") (pintype "passive"))
    )
    (net (code "44") (name "V-BUS_SOL") (class "Default")
      (node (ref "C19") (pin "1") (pinfunction "1_1") (pintype "passive"))
      (node (ref "C20") (pin "1") (pinfunction "1_1") (pintype "passive"))
      (node (ref "C25") (pin "1") (pinfunction "1_1") (pintype "passive"))
      (node (ref "C26") (pin "1") (pinfunction "1_1") (pintype "passive"))
      (node (ref "C31") (pin "1") (pinfunction "1_1") (pintype "passive"))
      (node (ref "C32") (pin "1") (pinfunction "1_1") (pintype "passive"))
      (node (ref "U10") (pin "2") (pinfunction "VIN_2") (pintype "passive"))
      (node (ref "U11") (pin "2") (pinfunction "VIN_2") (pintype "passive"))
      (node (ref "U6") (pin "2") (pinfunction "VIN_2") (pintype "passive"))
      (node (ref "U7") (pin "2") (pinfunction "VIN_2") (pintype "passive"))
      (node (ref "U8") (pin "2") (pinfunction "VIN_2") (pintype "passive"))
      (node (ref "U9") (pin "2") (pinfunction "VIN_2") (pintype "passive"))
    )
    (net (code "45") (name "V-POS5V") (class "Default")
      (node (ref "R19") (pin "1") (pinfunction "1_1") (pintype "passive"))
      (node (ref "R20") (pin "1") (pinfunction "1_1") (pintype "passive"))
      (node (ref "R27") (pin "1") (pinfunction "1_1") (pintype "passive"))
      (node (ref "R28") (pin "1") (pinfunction "1_1") (pintype "passive"))
      (node (ref "R35") (pin "1") (pinfunction "1_1") (pintype "passive"))
      (node (ref "R36") (pin "1") (pinfunction "1_1") (pintype "passive"))
      (node (ref "U10") (pin "7") (pinfunction "IN_7") (pintype "passive"))
      (node (ref "U11") (pin "7") (pinfunction "IN_7") (pintype "passive"))
      (node (ref "U6") (pin "7") (pinfunction "IN_7") (pintype "passive"))
      (node (ref "U7") (pin "7") (pinfunction "IN_7") (pintype "passive"))
      (node (ref "U8") (pin "7") (pinfunction "IN_7") (pintype "passive"))
      (node (ref "U9") (pin "7") (pinfunction "IN_7") (pintype "passive"))
    )
  )
)
